# 22_PCIE.net
KiCad netlist of a schematic drawn in Altium Designer
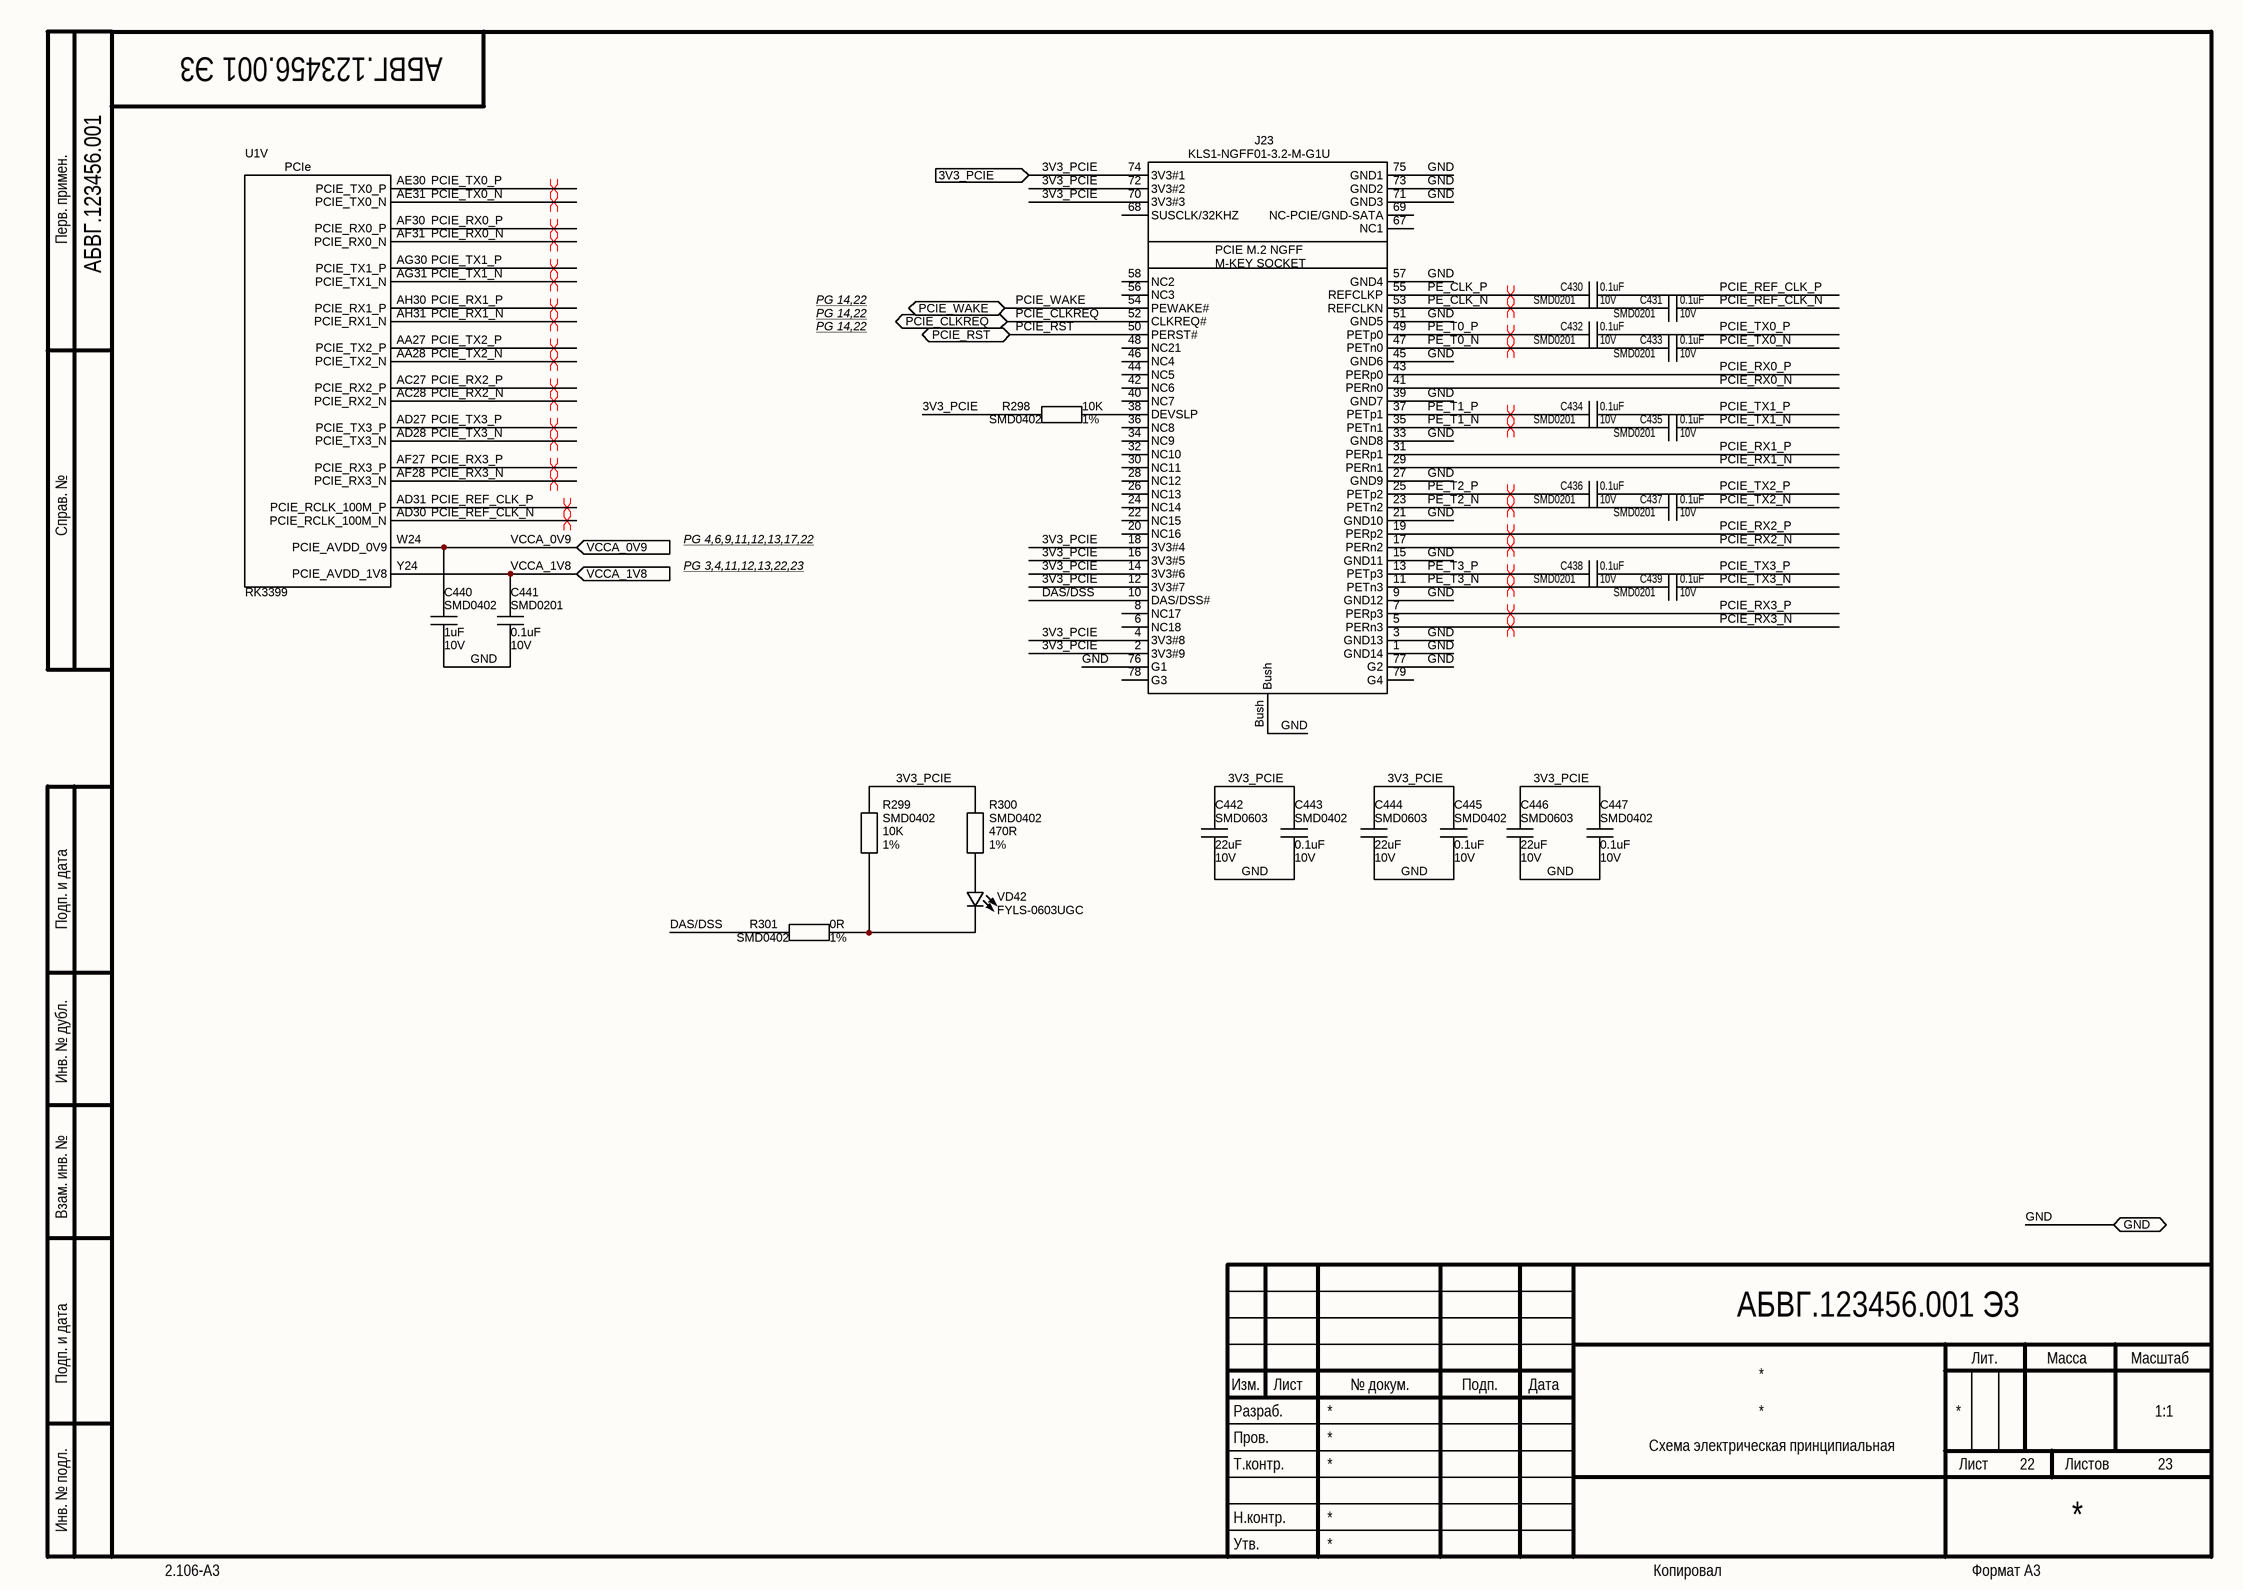
[diagram p0: 22 PCIE.SchDoc]

(export (version "E")
  (design (tool "Eeschema 10.0.6"))
  (components
    (comp (ref "C430")
      (value "0.1uF")
      (footprint "Didur_PcbLib_1:CAP_SMD_0201")
      (fields
        (field (name "PACKAGE") "SMD0201")
        (field (name "PARTNUMBER") "CC0201KRX5R6BB104")
        (field (name "VOLTAGE") "10V")
      )
      (libsource (lib "Didur_SchLib_1") (part "Ceramic_Cap"))
    )
    (comp (ref "C431")
      (value "0.1uF")
      (footprint "Didur_PcbLib_1:CAP_SMD_0201")
      (fields
        (field (name "PACKAGE") "SMD0201")
        (field (name "PARTNUMBER") "CC0201KRX5R6BB104")
        (field (name "VOLTAGE") "10V")
      )
      (libsource (lib "Didur_SchLib_1") (part "Ceramic_Cap"))
    )
    (comp (ref "C432")
      (value "0.1uF")
      (footprint "Didur_PcbLib_1:CAP_SMD_0201")
      (fields
        (field (name "PACKAGE") "SMD0201")
        (field (name "PARTNUMBER") "CC0201KRX5R6BB104")
        (field (name "VOLTAGE") "10V")
      )
      (libsource (lib "Didur_SchLib_1") (part "Ceramic_Cap"))
    )
    (comp (ref "C433")
      (value "0.1uF")
      (footprint "Didur_PcbLib_1:CAP_SMD_0201")
      (fields
        (field (name "PACKAGE") "SMD0201")
        (field (name "PARTNUMBER") "CC0201KRX5R6BB104")
        (field (name "VOLTAGE") "10V")
      )
      (libsource (lib "Didur_SchLib_1") (part "Ceramic_Cap"))
    )
    (comp (ref "C434")
      (value "0.1uF")
      (footprint "Didur_PcbLib_1:CAP_SMD_0201")
      (fields
        (field (name "PACKAGE") "SMD0201")
        (field (name "PARTNUMBER") "CC0201KRX5R6BB104")
        (field (name "VOLTAGE") "10V")
      )
      (libsource (lib "Didur_SchLib_1") (part "Ceramic_Cap"))
    )
    (comp (ref "C435")
      (value "0.1uF")
      (footprint "Didur_PcbLib_1:CAP_SMD_0201")
      (fields
        (field (name "PACKAGE") "SMD0201")
        (field (name "PARTNUMBER") "CC0201KRX5R6BB104")
        (field (name "VOLTAGE") "10V")
      )
      (libsource (lib "Didur_SchLib_1") (part "Ceramic_Cap"))
    )
    (comp (ref "C436")
      (value "0.1uF")
      (footprint "Didur_PcbLib_1:CAP_SMD_0201")
      (fields
        (field (name "PACKAGE") "SMD0201")
        (field (name "PARTNUMBER") "CC0201KRX5R6BB104")
        (field (name "VOLTAGE") "10V")
      )
      (libsource (lib "Didur_SchLib_1") (part "Ceramic_Cap"))
    )
    (comp (ref "C437")
      (value "0.1uF")
      (footprint "Didur_PcbLib_1:CAP_SMD_0201")
      (fields
        (field (name "PACKAGE") "SMD0201")
        (field (name "PARTNUMBER") "CC0201KRX5R6BB104")
        (field (name "VOLTAGE") "10V")
      )
      (libsource (lib "Didur_SchLib_1") (part "Ceramic_Cap"))
    )
    (comp (ref "C438")
      (value "0.1uF")
      (footprint "Didur_PcbLib_1:CAP_SMD_0201")
      (fields
        (field (name "PACKAGE") "SMD0201")
        (field (name "PARTNUMBER") "CC0201KRX5R6BB104")
        (field (name "VOLTAGE") "10V")
      )
      (libsource (lib "Didur_SchLib_1") (part "Ceramic_Cap"))
    )
    (comp (ref "C439")
      (value "0.1uF")
      (footprint "Didur_PcbLib_1:CAP_SMD_0201")
      (fields
        (field (name "PACKAGE") "SMD0201")
        (field (name "PARTNUMBER") "CC0201KRX5R6BB104")
        (field (name "VOLTAGE") "10V")
      )
      (libsource (lib "Didur_SchLib_1") (part "Ceramic_Cap"))
    )
    (comp (ref "C440")
      (value "1uF")
      (footprint "Didur_PcbLib_1:CAP_SMD_0402_small")
      (fields
        (field (name "PACKAGE") "SMD0402")
        (field (name "PARTNUMBER") "CC0402KRX5R6BB105")
        (field (name "VOLTAGE") "10V")
      )
      (libsource (lib "Didur_SchLib_1") (part "Ceramic_Cap"))
    )
    (comp (ref "C441")
      (value "0.1uF")
      (footprint "Didur_PcbLib_1:CAP_SMD_0201")
      (fields
        (field (name "PACKAGE") "SMD0201")
        (field (name "PARTNUMBER") "CC0201KRX5R6BB104")
        (field (name "VOLTAGE") "10V")
      )
      (libsource (lib "Didur_SchLib_1") (part "Ceramic_Cap"))
    )
    (comp (ref "C442")
      (value "22uF")
      (footprint "CAP_SMD_0603")
      (fields
        (field (name "PACKAGE") "SMD0603")
        (field (name "PARTNUMBER") "CL10A226MP8NUNE")
        (field (name "VOLTAGE") "10V")
      )
      (libsource (lib "Didur_SchLib_1") (part "Ceramic_Cap"))
    )
    (comp (ref "C443")
      (value "0.1uF")
      (footprint "Didur_PcbLib_1:CAP_SMD_0402")
      (fields
        (field (name "PACKAGE") "SMD0402")
        (field (name "PARTNUMBER") "CC0402KRX5R6BB104")
        (field (name "VOLTAGE") "10V")
      )
      (libsource (lib "Didur_SchLib_1") (part "Ceramic_Cap"))
    )
    (comp (ref "C444")
      (value "22uF")
      (footprint "CAP_SMD_0603")
      (fields
        (field (name "PACKAGE") "SMD0603")
        (field (name "PARTNUMBER") "CL10A226MP8NUNE")
        (field (name "VOLTAGE") "10V")
      )
      (libsource (lib "Didur_SchLib_1") (part "Ceramic_Cap"))
    )
    (comp (ref "C445")
      (value "0.1uF")
      (footprint "Didur_PcbLib_1:CAP_SMD_0402")
      (fields
        (field (name "PACKAGE") "SMD0402")
        (field (name "PARTNUMBER") "CC0402KRX5R6BB104")
        (field (name "VOLTAGE") "10V")
      )
      (libsource (lib "Didur_SchLib_1") (part "Ceramic_Cap"))
    )
    (comp (ref "C446")
      (value "22uF")
      (footprint "CAP_SMD_0603")
      (fields
        (field (name "PACKAGE") "SMD0603")
        (field (name "PARTNUMBER") "CL10A226MP8NUNE")
        (field (name "VOLTAGE") "10V")
      )
      (libsource (lib "Didur_SchLib_1") (part "Ceramic_Cap"))
    )
    (comp (ref "C447")
      (value "0.1uF")
      (footprint "Didur_PcbLib_1:CAP_SMD_0402")
      (fields
        (field (name "PACKAGE") "SMD0402")
        (field (name "PARTNUMBER") "CC0402KRX5R6BB104")
        (field (name "VOLTAGE") "10V")
      )
      (libsource (lib "Didur_SchLib_1") (part "Ceramic_Cap"))
    )
    (comp (ref "J23")
      (value "KLS1-NGFF01-3.2-M-G1U")
      (footprint "Didur_PcbLib_1:KLS1-NGFF01-3.2-M-G1U_42mm")
      (libsource (lib "Didur_SchLib_1") (part "KLS1-NGFF01-3.2-M-G1U_1"))
    )
    (comp (ref "R298")
      (value "10K")
      (footprint "Didur_PcbLib_1:RES_SMD_0402")
      (fields
        (field (name "PACKAGE") "SMD0402")
        (field (name "PARTNUMBER") "RC0402FR-0710KL")
        (field (name "TOLERANCE") "1%")
      )
      (libsource (lib "Didur_SchLib_1") (part "Chip_Res"))
    )
    (comp (ref "R299")
      (value "10K")
      (footprint "Didur_PcbLib_1:RES_SMD_0402")
      (fields
        (field (name "PACKAGE") "SMD0402")
        (field (name "PARTNUMBER") "RC0402FR-0710KL")
        (field (name "TOLERANCE") "1%")
      )
      (libsource (lib "") (part "Chip_Res_1"))
    )
    (comp (ref "R300")
      (value "470R")
      (footprint "Didur_PcbLib_1:RES_SMD_0402")
      (fields
        (field (name "PACKAGE") "SMD0402")
        (field (name "PARTNUMBER") "RC0402FR-07470RL")
        (field (name "TOLERANCE") "1%")
      )
      (libsource (lib "") (part "Chip_Res_1"))
    )
    (comp (ref "R301")
      (value "0R")
      (footprint "Didur_PcbLib_1:RES_SMD_0402")
      (fields
        (field (name "PACKAGE") "SMD0402")
        (field (name "PARTNUMBER") "RC0402FR-070RL")
        (field (name "TOLERANCE") "1%")
      )
      (libsource (lib "Didur_SchLib_1") (part "Chip_Res"))
    )
    (comp (ref "U1")
      (value "RK3399")
      (footprint "BGA828C65P31X31_2100X2100X161N")
      (fields (field (name "Comment") "RK3399_FF"))
      (libsource (lib "Didur_SchLib_1") (part "RK3399_FF"))
    )
    (comp (ref "VD42")
      (value "FYLS-0603UGC")
      (footprint "Didur_PcbLib_1:LED_0603")
      (libsource (lib "Didur_SchLib_1") (part "LED"))
    )
  )
  (nets
    (net (code "1") (name "/3V3_PCIE") (class "Default")
      (node (ref "C442") (pin "2") (pinfunction "2_2") (pintype "power_in"))
      (node (ref "C443") (pin "1") (pinfunction "1_1") (pintype "power_in"))
      (node (ref "C444") (pin "2") (pinfunction "2_2") (pintype "power_in"))
      (node (ref "C445") (pin "1") (pinfunction "1_1") (pintype "power_in"))
      (node (ref "C446") (pin "2") (pinfunction "2_2") (pintype "power_in"))
      (node (ref "C447") (pin "1") (pinfunction "1_1") (pintype "power_in"))
      (node (ref "J23") (pin "12") (pinfunction "3V3#7_12") (pintype "passive"))
      (node (ref "J23") (pin "14") (pinfunction "3V3#6_14") (pintype "passive"))
      (node (ref "J23") (pin "16") (pinfunction "3V3#5_16") (pintype "passive"))
      (node (ref "J23") (pin "18") (pinfunction "3V3#4_18") (pintype "passive"))
      (node (ref "J23") (pin "2") (pinfunction "3V3#9_2") (pintype "passive"))
      (node (ref "J23") (pin "4") (pinfunction "3V3#8_4") (pintype "passive"))
      (node (ref "J23") (pin "70") (pinfunction "3V3#3_70") (pintype "passive"))
      (node (ref "J23") (pin "72") (pinfunction "3V3#2_72") (pintype "passive"))
      (node (ref "J23") (pin "74") (pinfunction "3V3#1_74") (pintype "passive"))
      (node (ref "R298") (pin "2") (pinfunction "2_2") (pintype "passive"))
      (node (ref "R299") (pin "2") (pinfunction "2_2") (pintype "passive"))
      (node (ref "R300") (pin "2") (pinfunction "2_2") (pintype "passive"))
    )
    (net (code "2") (name "/DAS{slash}DSS") (class "Default")
      (node (ref "J23") (pin "10") (pinfunction "DAS/DSS#_10") (pintype "passive"))
      (node (ref "R301") (pin "2") (pinfunction "2_2") (pintype "passive"))
    )
    (net (code "3") (name "/GND") (class "Default")
      (node (ref "C440") (pin "2") (pinfunction "2_2") (pintype "power_in"))
      (node (ref "C441") (pin "2") (pinfunction "2_2") (pintype "power_in"))
      (node (ref "C442") (pin "1") (pinfunction "1_1") (pintype "power_in"))
      (node (ref "C443") (pin "2") (pinfunction "2_2") (pintype "power_in"))
      (node (ref "C444") (pin "1") (pinfunction "1_1") (pintype "power_in"))
      (node (ref "C445") (pin "2") (pinfunction "2_2") (pintype "power_in"))
      (node (ref "C446") (pin "1") (pinfunction "1_1") (pintype "power_in"))
      (node (ref "C447") (pin "2") (pinfunction "2_2") (pintype "power_in"))
      (node (ref "J23") (pin "1") (pinfunction "GND14_1") (pintype "passive"))
      (node (ref "J23") (pin "15") (pinfunction "GND11_15") (pintype "passive"))
      (node (ref "J23") (pin "21") (pinfunction "GND10_21") (pintype "passive"))
      (node (ref "J23") (pin "27") (pinfunction "GND9_27") (pintype "passive"))
      (node (ref "J23") (pin "3") (pinfunction "GND13_3") (pintype "passive"))
      (node (ref "J23") (pin "33") (pinfunction "GND8_33") (pintype "passive"))
      (node (ref "J23") (pin "39") (pinfunction "GND7_39") (pintype "passive"))
      (node (ref "J23") (pin "45") (pinfunction "GND6_45") (pintype "passive"))
      (node (ref "J23") (pin "51") (pinfunction "GND5_51") (pintype "passive"))
      (node (ref "J23") (pin "57") (pinfunction "GND4_57") (pintype "passive"))
      (node (ref "J23") (pin "71") (pinfunction "GND3_71") (pintype "passive"))
      (node (ref "J23") (pin "73") (pinfunction "GND2_73") (pintype "passive"))
      (node (ref "J23") (pin "75") (pinfunction "GND1_75") (pintype "passive"))
      (node (ref "J23") (pin "76") (pinfunction "G1_76") (pintype "passive"))
      (node (ref "J23") (pin "77") (pinfunction "G2_77") (pintype "passive"))
      (node (ref "J23") (pin "9") (pinfunction "GND12_9") (pintype "passive"))
      (node (ref "J23") (pin "Bush") (pinfunction "Bush_Bush") (pintype "passive"))
    )
    (net (code "4") (name "/PCIE_CLKREQ") (class "Default")
      (node (ref "J23") (pin "52") (pinfunction "CLKREQ#_52") (pintype "passive"))
    )
    (net (code "5") (name "/PCIE_REF_CLK_N") (class "Default")
      (node (ref "C431") (pin "1") (pinfunction "1_1") (pintype "power_in"))
      (node (ref "U1") (pin "AD30") (pinfunction "PCIE_RCLK_100M_N_AD30") (pintype "passive"))
    )
    (net (code "6") (name "/PCIE_REF_CLK_P") (class "Default")
      (node (ref "C430") (pin "1") (pinfunction "1_1") (pintype "power_in"))
      (node (ref "U1") (pin "AD31") (pinfunction "PCIE_RCLK_100M_P_AD31") (pintype "passive"))
    )
    (net (code "7") (name "/PCIE_RST") (class "Default")
      (node (ref "J23") (pin "50") (pinfunction "PERST#_50") (pintype "passive"))
    )
    (net (code "8") (name "/PCIE_RX0_N") (class "Default")
      (node (ref "J23") (pin "41") (pinfunction "PERn0_41") (pintype "passive"))
      (node (ref "U1") (pin "AF31") (pinfunction "PCIE_RX0_N_AF31") (pintype "passive"))
    )
    (net (code "9") (name "/PCIE_RX0_P") (class "Default")
      (node (ref "J23") (pin "43") (pinfunction "PERp0_43") (pintype "passive"))
      (node (ref "U1") (pin "AF30") (pinfunction "PCIE_RX0_P_AF30") (pintype "passive"))
    )
    (net (code "10") (name "/PCIE_RX1_N") (class "Default")
      (node (ref "J23") (pin "29") (pinfunction "PERn1_29") (pintype "passive"))
      (node (ref "U1") (pin "AH31") (pinfunction "PCIE_RX1_N_AH31") (pintype "passive"))
    )
    (net (code "11") (name "/PCIE_RX1_P") (class "Default")
      (node (ref "J23") (pin "31") (pinfunction "PERp1_31") (pintype "passive"))
      (node (ref "U1") (pin "AH30") (pinfunction "PCIE_RX1_P_AH30") (pintype "passive"))
    )
    (net (code "12") (name "/PCIE_RX2_N") (class "Default")
      (node (ref "J23") (pin "17") (pinfunction "PERn2_17") (pintype "passive"))
      (node (ref "U1") (pin "AC28") (pinfunction "PCIE_RX2_N_AC28") (pintype "passive"))
    )
    (net (code "13") (name "/PCIE_RX2_P") (class "Default")
      (node (ref "J23") (pin "19") (pinfunction "PERp2_19") (pintype "passive"))
      (node (ref "U1") (pin "AC27") (pinfunction "PCIE_RX2_P_AC27") (pintype "passive"))
    )
    (net (code "14") (name "/PCIE_RX3_N") (class "Default")
      (node (ref "J23") (pin "5") (pinfunction "PERn3_5") (pintype "passive"))
      (node (ref "U1") (pin "AF28") (pinfunction "PCIE_RX3_N_AF28") (pintype "passive"))
    )
    (net (code "15") (name "/PCIE_RX3_P") (class "Default")
      (node (ref "J23") (pin "7") (pinfunction "PERp3_7") (pintype "passive"))
      (node (ref "U1") (pin "AF27") (pinfunction "PCIE_RX3_P_AF27") (pintype "passive"))
    )
    (net (code "16") (name "/PCIE_TX0_N") (class "Default")
      (node (ref "C433") (pin "1") (pinfunction "1_1") (pintype "power_in"))
      (node (ref "U1") (pin "AE31") (pinfunction "PCIE_TX0_N_AE31") (pintype "passive"))
    )
    (net (code "17") (name "/PCIE_TX0_P") (class "Default")
      (node (ref "C432") (pin "1") (pinfunction "1_1") (pintype "power_in"))
      (node (ref "U1") (pin "AE30") (pinfunction "PCIE_TX0_P_AE30") (pintype "passive"))
    )
    (net (code "18") (name "/PCIE_TX1_N") (class "Default")
      (node (ref "C435") (pin "1") (pinfunction "1_1") (pintype "power_in"))
      (node (ref "U1") (pin "AG31") (pinfunction "PCIE_TX1_N_AG31") (pintype "passive"))
    )
    (net (code "19") (name "/PCIE_TX1_P") (class "Default")
      (node (ref "C434") (pin "1") (pinfunction "1_1") (pintype "power_in"))
      (node (ref "U1") (pin "AG30") (pinfunction "PCIE_TX1_P_AG30") (pintype "passive"))
    )
    (net (code "20") (name "/PCIE_TX2_N") (class "Default")
      (node (ref "C437") (pin "1") (pinfunction "1_1") (pintype "power_in"))
      (node (ref "U1") (pin "AA28") (pinfunction "PCIE_TX2_N_AA28") (pintype "passive"))
    )
    (net (code "21") (name "/PCIE_TX2_P") (class "Default")
      (node (ref "C436") (pin "1") (pinfunction "1_1") (pintype "power_in"))
      (node (ref "U1") (pin "AA27") (pinfunction "PCIE_TX2_P_AA27") (pintype "passive"))
    )
    (net (code "22") (name "/PCIE_TX3_N") (class "Default")
      (node (ref "C439") (pin "1") (pinfunction "1_1") (pintype "power_in"))
      (node (ref "U1") (pin "AD28") (pinfunction "PCIE_TX3_N_AD28") (pintype "passive"))
    )
    (net (code "23") (name "/PCIE_TX3_P") (class "Default")
      (node (ref "C438") (pin "1") (pinfunction "1_1") (pintype "power_in"))
      (node (ref "U1") (pin "AD27") (pinfunction "PCIE_TX3_P_AD27") (pintype "passive"))
    )
    (net (code "24") (name "/PCIE_WAKE") (class "Default")
      (node (ref "J23") (pin "54") (pinfunction "PEWAKE#_54") (pintype "passive"))
    )
    (net (code "25") (name "/PE_CLK_N") (class "Default")
      (node (ref "C431") (pin "2") (pinfunction "2_2") (pintype "power_in"))
      (node (ref "J23") (pin "53") (pinfunction "REFCLKN_53") (pintype "passive"))
    )
    (net (code "26") (name "/PE_CLK_P") (class "Default")
      (node (ref "C430") (pin "2") (pinfunction "2_2") (pintype "power_in"))
      (node (ref "J23") (pin "55") (pinfunction "REFCLKP_55") (pintype "passive"))
    )
    (net (code "27") (name "/PE_T0_N") (class "Default")
      (node (ref "C433") (pin "2") (pinfunction "2_2") (pintype "power_in"))
      (node (ref "J23") (pin "47") (pinfunction "PETn0_47") (pintype "passive"))
    )
    (net (code "28") (name "/PE_T0_P") (class "Default")
      (node (ref "C432") (pin "2") (pinfunction "2_2") (pintype "power_in"))
      (node (ref "J23") (pin "49") (pinfunction "PETp0_49") (pintype "passive"))
    )
    (net (code "29") (name "/PE_T1_N") (class "Default")
      (node (ref "C435") (pin "2") (pinfunction "2_2") (pintype "power_in"))
      (node (ref "J23") (pin "35") (pinfunction "PETn1_35") (pintype "passive"))
    )
    (net (code "30") (name "/PE_T1_P") (class "Default")
      (node (ref "C434") (pin "2") (pinfunction "2_2") (pintype "power_in"))
      (node (ref "J23") (pin "37") (pinfunction "PETp1_37") (pintype "passive"))
    )
    (net (code "31") (name "/PE_T2_N") (class "Default")
      (node (ref "C437") (pin "2") (pinfunction "2_2") (pintype "power_in"))
      (node (ref "J23") (pin "23") (pinfunction "PETn2_23") (pintype "passive"))
    )
    (net (code "32") (name "/PE_T2_P") (class "Default")
      (node (ref "C436") (pin "2") (pinfunction "2_2") (pintype "power_in"))
      (node (ref "J23") (pin "25") (pinfunction "PETp2_25") (pintype "passive"))
    )
    (net (code "33") (name "/PE_T3_N") (class "Default")
      (node (ref "C439") (pin "2") (pinfunction "2_2") (pintype "power_in"))
      (node (ref "J23") (pin "11") (pinfunction "PETn3_11") (pintype "passive"))
    )
    (net (code "34") (name "/PE_T3_P") (class "Default")
      (node (ref "C438") (pin "2") (pinfunction "2_2") (pintype "power_in"))
      (node (ref "J23") (pin "13") (pinfunction "PETp3_13") (pintype "passive"))
    )
    (net (code "35") (name "/VCCA_0V9") (class "Default")
      (node (ref "C440") (pin "1") (pinfunction "1_1") (pintype "power_in"))
      (node (ref "U1") (pin "W24") (pinfunction "PCIE_AVDD_0V9_W24") (pintype "passive"))
    )
    (net (code "36") (name "/VCCA_1V8") (class "Default")
      (node (ref "C441") (pin "1") (pinfunction "1_1") (pintype "power_in"))
      (node (ref "U1") (pin "Y24") (pinfunction "PCIE_AVDD_1V8_Y24") (pintype "passive"))
    )
    (net (code "37") (name "Net-(J23-DEVSLP)") (class "Default")
      (node (ref "J23") (pin "38") (pinfunction "DEVSLP_38") (pintype "passive"))
      (node (ref "R298") (pin "1") (pinfunction "1_1") (pintype "passive"))
    )
    (net (code "38") (name "Net-(VD42-A)") (class "Default")
      (node (ref "R300") (pin "1") (pinfunction "1_1") (pintype "passive"))
      (node (ref "VD42") (pin "1") (pinfunction "A_1") (pintype "passive"))
    )
    (net (code "39") (name "Net-(VD42-C)") (class "Default")
      (node (ref "R299") (pin "1") (pinfunction "1_1") (pintype "passive"))
      (node (ref "R301") (pin "1") (pinfunction "1_1") (pintype "passive"))
      (node (ref "VD42") (pin "2") (pinfunction "C_2") (pintype "passive"))
    )
    (net (code "40") (name "unconnected-(J23-G3-Pad78)") (class "Default")
      (node (ref "J23") (pin "78") (pinfunction "G3_78") (pintype "passive"))
    )
    (net (code "41") (name "unconnected-(J23-G4-Pad79)") (class "Default")
      (node (ref "J23") (pin "79") (pinfunction "G4_79") (pintype "passive"))
    )
    (net (code "42") (name "unconnected-(J23-NC-PCIE{slash}GND-SATA-Pad69)") (class "Default")
      (node (ref "J23") (pin "69") (pinfunction "NC-PCIE/GND-SATA_69") (pintype "passive"))
    )
    (net (code "43") (name "unconnected-(J23-NC1-Pad67)") (class "Default")
      (node (ref "J23") (pin "67") (pinfunction "NC1_67") (pintype "passive"))
    )
    (net (code "44") (name "unconnected-(J23-NC2-Pad58)") (class "Default")
      (node (ref "J23") (pin "58") (pinfunction "NC2_58") (pintype "passive"))
    )
    (net (code "45") (name "unconnected-(J23-NC3-Pad56)") (class "Default")
      (node (ref "J23") (pin "56") (pinfunction "NC3_56") (pintype "passive"))
    )
    (net (code "46") (name "unconnected-(J23-NC4-Pad46)") (class "Default")
      (node (ref "J23") (pin "46") (pinfunction "NC4_46") (pintype "passive"))
    )
    (net (code "47") (name "unconnected-(J23-NC5-Pad44)") (class "Default")
      (node (ref "J23") (pin "44") (pinfunction "NC5_44") (pintype "passive"))
    )
    (net (code "48") (name "unconnected-(J23-NC6-Pad42)") (class "Default")
      (node (ref "J23") (pin "42") (pinfunction "NC6_42") (pintype "passive"))
    )
    (net (code "49") (name "unconnected-(J23-NC7-Pad40)") (class "Default")
      (node (ref "J23") (pin "40") (pinfunction "NC7_40") (pintype "passive"))
    )
    (net (code "50") (name "unconnected-(J23-NC8-Pad36)") (class "Default")
      (node (ref "J23") (pin "36") (pinfunction "NC8_36") (pintype "passive"))
    )
    (net (code "51") (name "unconnected-(J23-NC9-Pad34)") (class "Default")
      (node (ref "J23") (pin "34") (pinfunction "NC9_34") (pintype "passive"))
    )
    (net (code "52") (name "unconnected-(J23-NC10-Pad32)") (class "Default")
      (node (ref "J23") (pin "32") (pinfunction "NC10_32") (pintype "passive"))
    )
    (net (code "53") (name "unconnected-(J23-NC11-Pad30)") (class "Default")
      (node (ref "J23") (pin "30") (pinfunction "NC11_30") (pintype "passive"))
    )
    (net (code "54") (name "unconnected-(J23-NC12-Pad28)") (class "Default")
      (node (ref "J23") (pin "28") (pinfunction "NC12_28") (pintype "passive"))
    )
    (net (code "55") (name "unconnected-(J23-NC13-Pad26)") (class "Default")
      (node (ref "J23") (pin "26") (pinfunction "NC13_26") (pintype "passive"))
    )
    (net (code "56") (name "unconnected-(J23-NC14-Pad24)") (class "Default")
      (node (ref "J23") (pin "24") (pinfunction "NC14_24") (pintype "passive"))
    )
    (net (code "57") (name "unconnected-(J23-NC15-Pad22)") (class "Default")
      (node (ref "J23") (pin "22") (pinfunction "NC15_22") (pintype "passive"))
    )
    (net (code "58") (name "unconnected-(J23-NC16-Pad20)") (class "Default")
      (node (ref "J23") (pin "20") (pinfunction "NC16_20") (pintype "passive"))
    )
    (net (code "59") (name "unconnected-(J23-NC17-Pad8)") (class "Default")
      (node (ref "J23") (pin "8") (pinfunction "NC17_8") (pintype "passive"))
    )
    (net (code "60") (name "unconnected-(J23-NC18-Pad6)") (class "Default")
      (node (ref "J23") (pin "6") (pinfunction "NC18_6") (pintype "passive"))
    )
    (net (code "61") (name "unconnected-(J23-NC21-Pad48)") (class "Default")
      (node (ref "J23") (pin "48") (pinfunction "NC21_48") (pintype "passive"))
    )
    (net (code "62") (name "unconnected-(J23-SUSCLK{slash}32KHZ-Pad68)") (class "Default")
      (node (ref "J23") (pin "68") (pinfunction "SUSCLK/32KHZ_68") (pintype "passive"))
    )
  )
)
